# analog_front_end.net
KiCad netlist of a schematic drawn in Altium Designer
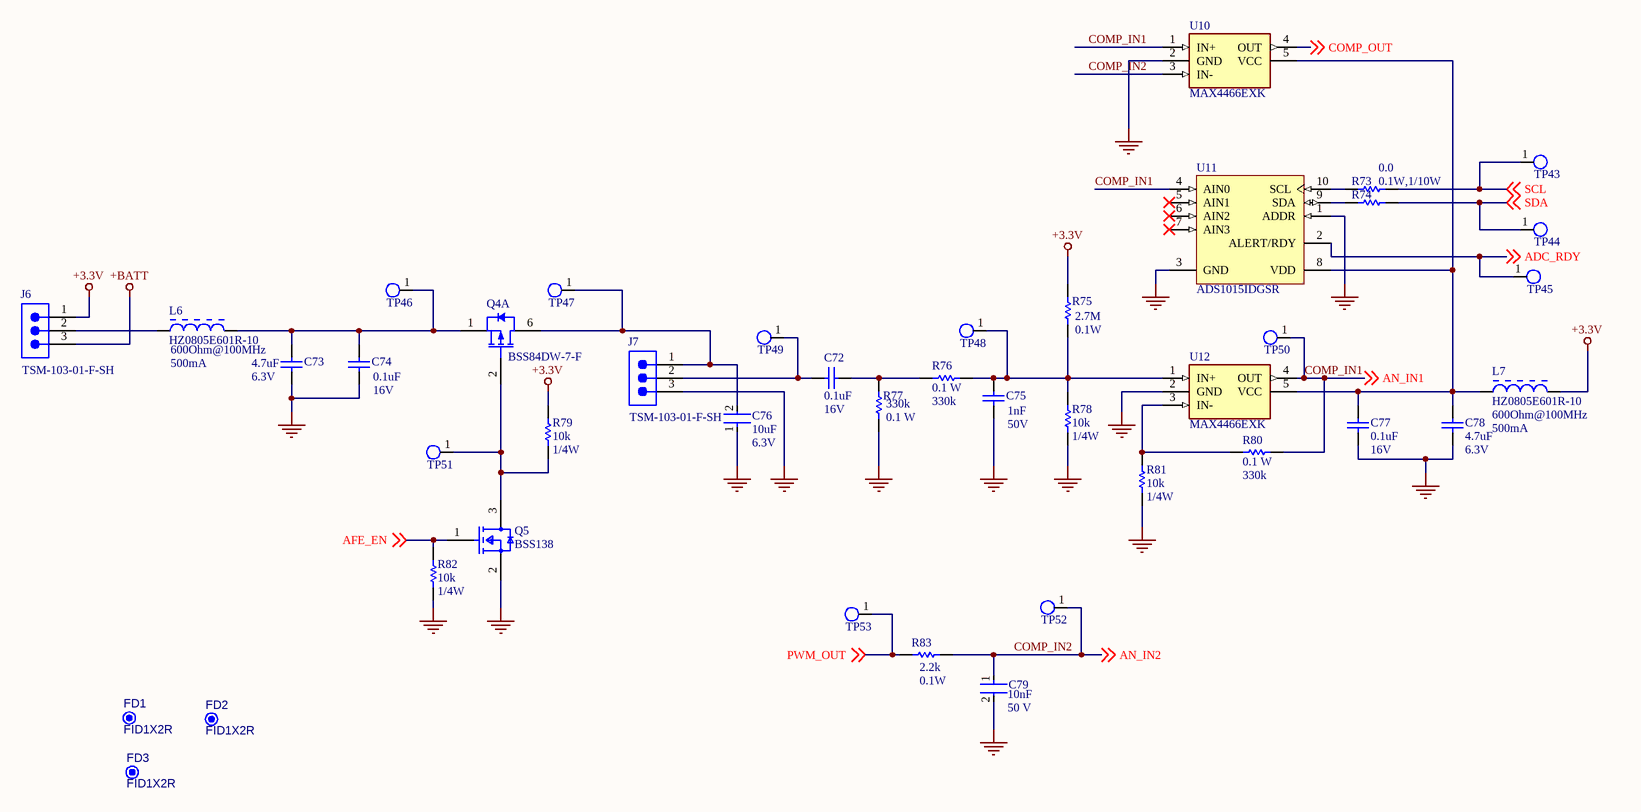
[diagram p0: analog_front_end.SchDoc]

(export (version "E")
  (design (tool "Eeschema 10.0.6"))
  (components
    (comp (ref "C72")
      (value "0.1uF")
      (footprint "CAPC1608X87X35ML15T15")
      (description "Ceramic Capacitor 0.1uF 16V +-10% X7R0603")
      (fields
        (field (name "PART NUMBER") "C0603C104M4RACTU")
        (field (name "MANUFACTURER") "Kemet")
        (field (name "VOLTAGE") "16V")
      )
      (libsource (lib "Altium Content Vault") (part "CAP"))
    )
    (comp (ref "C73")
      (value "4.7uF")
      (footprint "CAPC2013X145X50NL20T25")
      (fields
        (field (name "PART NUMBER") "C0805C475K9PACTU")
        (field (name "MANUFACTURER") "Kemet")
        (field (name "VOLTAGE") "6.3V")
      )
      (libsource (lib "Altium Content Vault") (part "CAP"))
    )
    (comp (ref "C74")
      (value "0.1uF")
      (footprint "CAPC1608X87X35ML15T15")
      (description "Ceramic Capacitor 0.1uF 16V +-10% X7R0603")
      (fields
        (field (name "PART NUMBER") "C0603C104M4RACTU")
        (field (name "MANUFACTURER") "Kemet")
        (field (name "VOLTAGE") "16V")
      )
      (libsource (lib "Altium Content Vault") (part "CAP"))
    )
    (comp (ref "C75")
      (value "1nF")
      (footprint "CAPC1608X90X35LL15T15")
      (fields
        (field (name "MANUFACTURER") "AVX Interconnect / Elco")
        (field (name "PART NUMBER") "06035C102KAT2A")
        (field (name "VOLTAGE") "50V")
      )
      (libsource (lib "Altium Content Vault") (part "CAP"))
    )
    (comp (ref "C76")
      (value "10uF")
      (footprint "FP-CL10-IPC_C")
      (description "Cap Ceramic 10uF 6.3V X5R ±20% Pad SMD 0603 +85°C T/R")
      (fields
        (field (name "VOLTAGE") "6.3V")
        (field (name "TOLERANCE") "20%")
        (field (name "MANUFACTURER") "Samsung")
      )
      (libsource (lib "Altium Content Vault") (part "b4654b650e69147ec39a6b967a45e02"))
    )
    (comp (ref "C77")
      (value "0.1uF")
      (footprint "CAPC1608X87X35ML15T15")
      (description "Ceramic Capacitor 0.1uF 16V +-10% X7R0603")
      (fields
        (field (name "PART NUMBER") "C0603C104M4RACTU")
        (field (name "MANUFACTURER") "Kemet")
        (field (name "VOLTAGE") "16V")
      )
      (libsource (lib "Altium Content Vault") (part "CAP"))
    )
    (comp (ref "C78")
      (value "4.7uF")
      (footprint "CAPC2013X145X50NL20T25")
      (fields
        (field (name "PART NUMBER") "C0805C475K9PACTU")
        (field (name "MANUFACTURER") "Kemet")
        (field (name "VOLTAGE") "6.3V")
      )
      (libsource (lib "Altium Content Vault") (part "CAP"))
    )
    (comp (ref "C79")
      (value "10nF")
      (footprint "FP-C0805C-DN-MFG")
      (description "CAP CER 10000PF 50V X7R 0805")
      (fields
        (field (name "VOLTAGE") "50 V")
        (field (name "PART NUMBER") "C0805C103K5RACAUTO")
        (field (name "MANUFACTURER") "KEMET")
      )
      (libsource (lib "Altium Content Vault") (part "b4654b650e69147ec39a6b967a45e02"))
    )
    (comp (ref "FD1")
      (value "FID1X2R")
      (footprint "FID1X2R")
      (description "Fiducial - Round 1x2mm")
      (libsource (lib "EMS") (part "CMP-00134-2"))
    )
    (comp (ref "FD2")
      (value "FID1X2R")
      (footprint "FID1X2R")
      (description "Fiducial - Round 1x2mm")
      (libsource (lib "EMS") (part "CMP-00134-2"))
    )
    (comp (ref "FD3")
      (value "FID1X2R")
      (footprint "FID1X2R")
      (description "Fiducial - Round 1x2mm")
      (libsource (lib "EMS") (part "CMP-00134-2"))
    )
    (comp (ref "J6")
      (value "TSM-103-01-F-SH")
      (footprint "SMTC-TSM-103-01-X-SH-A")
      (fields (field (name "MANUFACTURER") "Samtec") (field (name "PART NUMBER") "TSM-103-01-F-SH"))
      (libsource (lib "Altium Content Vault") (part "SMTC-TSM-103-01-X-SH-A"))
    )
    (comp (ref "J7")
      (value "TSM-103-01-F-SH")
      (footprint "SMTC-TSM-103-01-X-SH-A")
      (fields (field (name "MANUFACTURER") "Samtec") (field (name "PART NUMBER") "TSM-103-01-F-SH"))
      (libsource (lib "Altium Content Vault") (part "SMTC-TSM-103-01-X-SH-A"))
    )
    (comp (ref "L6")
      (value "HZ0805E601R-10")
      (footprint "LIRD-LI0805H151R-10-2_V")
      (fields
        (field (name "IMPEDANCE @ FREQUENCY") "600Ohm@100MHz")
        (field (name "MANUFACTURER") "Laird")
        (field (name "CURRENT RATING (MAX)") "500mA")
      )
      (libsource (lib "Altium Content Vault") (part "IND-FB-2"))
    )
    (comp (ref "L7")
      (value "HZ0805E601R-10")
      (footprint "LIRD-LI0805H151R-10-2_V")
      (fields
        (field (name "IMPEDANCE @ FREQUENCY") "600Ohm@100MHz")
        (field (name "MANUFACTURER") "Laird")
        (field (name "CURRENT RATING (MAX)") "500mA")
      )
      (libsource (lib "") (part "IND-FB-2_1"))
    )
    (comp (ref "Q4")
      (value "BSS84DW-7-F")
      (footprint "DIOD-SOT363-6_V")
      (description "Dual P-Channel Enhancement Mode MOSFET, 50 VDS, -55 to 150 degC, 6-Pin SOT363, RoHS, Tape and Reel")
      (fields (field (name "MANUFACTURER") "DiodesIncorporated"))
      (libsource (lib "Altium Content Vault") (part "PEMOS-SGD-SGD-6"))
    )
    (comp (ref "Q5")
      (value "BSS138")
      (footprint "FP-318-08-IPC_B")
      (description "MOSFET N-CH 50V 220MA SOT-23")
      (libsource (lib "Altium Content Vault") (part "3b9c635fedb024a5347a57b145af9cc"))
    )
    (comp (ref "R73")
      (value "0.0")
      (footprint "RESC1608X55X35LL10T10")
      (description "Chip Resistor, 0 Ohm, +/- 5%, 0.1 W, -55 to 155 degC, 0603 (1608 Metric), RoHS, Tape and Reel")
      (fields
        (field (name "POWER") "0.1W,1/10W")
        (field (name "MANUFACTURER") "Samsung-Electro-Mechanics-America,-Inc.")
        (field (name "TOLERANCE") "Jumper")
      )
      (libsource (lib "Altium Content Vault") (part "RES-2"))
    )
    (comp (ref "R74")
      (value "RC1608J000CS")
      (footprint "RESC1608X55X35LL10T10")
      (description "Chip Resistor, 0 Ohm, +/- 5%, 0.1 W, -55 to 155 degC, 0603 (1608 Metric), RoHS, Tape and Reel")
      (fields
        (field (name "POWER") "0.1W,1/10W")
        (field (name "MANUFACTURER") "Samsung-Electro-Mechanics-America,-Inc.")
      )
      (libsource (lib "Altium Content Vault") (part "RES-2"))
    )
    (comp (ref "R75")
      (value "2.7M")
      (footprint "RESC1609X50X30ML10T20")
      (fields
        (field (name "PART NUMBER") "CRCW06032M70JNEA")
        (field (name "MANUFACTURER") "Vishay Dale")
        (field (name "POWER") "0.1W")
      )
      (libsource (lib "Altium Content Vault") (part "RES"))
    )
    (comp (ref "R76")
      (value "330k")
      (footprint "RESC0603(1608)_M")
      (description "330K 0.1W 1% 0603 (1608 Metric)  SMD")
      (fields
        (field (name "POWER") "0.1 W")
        (field (name "TOLERANCE") "1 %")
        (field (name "Comment") "330K 1% 0603(1608)")
      )
      (libsource (lib "Altium Content Vault") (part "RES"))
    )
    (comp (ref "R77")
      (value "330k")
      (footprint "RESC0603(1608)_M")
      (description "330K 0.1W 1% 0603 (1608 Metric)  SMD")
      (fields
        (field (name "POWER") "0.1 W")
        (field (name "TOLERANCE") "1 %")
        (field (name "Comment") "330K 1% 0603(1608)")
      )
      (libsource (lib "Altium Content Vault") (part "RES"))
    )
    (comp (ref "R78")
      (value "10k")
      (footprint "RESC3216X70X50NL05T20")
      (description "Res Thick Film 1206 10k Ohms 5% 1/4W")
      (fields
        (field (name "PART NUMBER") "ERJ-8GEYJ103V")
        (field (name "MANUFACTURER") "Panasonic")
        (field (name "POWER") "1/4W")
      )
      (libsource (lib "Altium Content Vault") (part "RES"))
    )
    (comp (ref "R79")
      (value "10k")
      (footprint "RESC3216X70X50NL05T20")
      (description "Res Thick Film 1206 10k Ohms 5% 1/4W")
      (fields
        (field (name "PART NUMBER") "ERJ-8GEYJ103V")
        (field (name "MANUFACTURER") "Panasonic")
        (field (name "POWER") "1/4W")
      )
      (libsource (lib "Altium Content Vault") (part "RES"))
    )
    (comp (ref "R80")
      (value "330k")
      (footprint "RESC0603(1608)_M")
      (description "330K 0.1W 1% 0603 (1608 Metric)  SMD")
      (fields
        (field (name "POWER") "0.1 W")
        (field (name "TOLERANCE") "1 %")
        (field (name "Comment") "330K 1% 0603(1608)")
      )
      (libsource (lib "Altium Content Vault") (part "RES"))
    )
    (comp (ref "R81")
      (value "10k")
      (footprint "RESC3216X70X50NL05T20")
      (description "Res Thick Film 1206 10k Ohms 5% 1/4W")
      (fields
        (field (name "PART NUMBER") "ERJ-8GEYJ103V")
        (field (name "MANUFACTURER") "Panasonic")
        (field (name "POWER") "1/4W")
      )
      (libsource (lib "Altium Content Vault") (part "RES"))
    )
    (comp (ref "R82")
      (value "10k")
      (footprint "RESC3216X70X50NL05T20")
      (description "Res Thick Film 1206 10k Ohms 5% 1/4W")
      (fields
        (field (name "PART NUMBER") "ERJ-8GEYJ103V")
        (field (name "MANUFACTURER") "Panasonic")
        (field (name "POWER") "1/4W")
      )
      (libsource (lib "Altium Content Vault") (part "RES"))
    )
    (comp (ref "R83")
      (value "2.2k")
      (footprint "RESC1608X55X25LL10T15")
      (fields
        (field (name "TOLERANCE") "1%")
        (field (name "VOLTAGE") "50V")
        (field (name "MANUFACTURER") "Yageo")
        (field (name "POWER") "0.1W")
      )
      (libsource (lib "Altium Content Vault") (part "RES-2"))
    )
    (comp (ref "TP43")
      (value "Test_Point_SMD")
      (footprint "Test_Point_SMD")
      (libsource (lib "Edson") (part "Test_Point_SMD"))
    )
    (comp (ref "TP44")
      (value "Test_Point_SMD")
      (footprint "Test_Point_SMD")
      (libsource (lib "Edson") (part "Test_Point_SMD"))
    )
    (comp (ref "TP45")
      (value "Test_Point_SMD")
      (footprint "Test_Point_SMD")
      (libsource (lib "Edson") (part "Test_Point_SMD"))
    )
    (comp (ref "TP46")
      (value "Test_Point_SMD")
      (footprint "Test_Point_SMD")
      (libsource (lib "Edson") (part "Test_Point_SMD"))
    )
    (comp (ref "TP47")
      (value "Test_Point_SMD")
      (footprint "Test_Point_SMD")
      (libsource (lib "Edson") (part "Test_Point_SMD"))
    )
    (comp (ref "TP48")
      (value "Test_Point_SMD")
      (footprint "Test_Point_SMD")
      (libsource (lib "Edson") (part "Test_Point_SMD"))
    )
    (comp (ref "TP49")
      (value "Test_Point_SMD")
      (footprint "Test_Point_SMD")
      (libsource (lib "Edson") (part "Test_Point_SMD"))
    )
    (comp (ref "TP50")
      (value "Test_Point_SMD")
      (footprint "Test_Point_SMD")
      (libsource (lib "Edson") (part "Test_Point_SMD"))
    )
    (comp (ref "TP51")
      (value "Test_Point_SMD")
      (footprint "Test_Point_SMD")
      (libsource (lib "Edson") (part "Test_Point_SMD"))
    )
    (comp (ref "TP52")
      (value "Test_Point_SMD")
      (footprint "Test_Point_SMD")
      (libsource (lib "Edson") (part "Test_Point_SMD"))
    )
    (comp (ref "TP53")
      (value "Test_Point_SMD")
      (footprint "Test_Point_SMD")
      (libsource (lib "Edson") (part "Test_Point_SMD"))
    )
    (comp (ref "U10")
      (value "MAX4466EXK")
      (footprint "SamacSys:SOT95P280X145-5N")
      (description "Integrated Circuit")
      (libsource (lib "*") (part "MAX4466EXK"))
    )
    (comp (ref "U11")
      (value "ADS1015IDGSR")
      (footprint "TI-DGS10_N")
      (fields (field (name "MANUFACTURER") "Texas Instruments"))
      (libsource (lib "Altium Content Vault") (part "TI-ADS1015_1115-10"))
    )
    (comp (ref "U12")
      (value "MAX4466EXK")
      (footprint "SamacSys:SOT95P280X145-5N")
      (description "Integrated Circuit")
      (libsource (lib "*") (part "MAX4466EXK"))
    )
  )
  (nets
    (net (code "1") (name "+3.3V") (class "Default")
      (node (ref "J6") (pin "1") (pinfunction "1_1") (pintype "passive"))
      (node (ref "L7") (pin "1") (pinfunction "1_1") (pintype "passive"))
      (node (ref "R75") (pin "2") (pinfunction "2_2") (pintype "passive"))
      (node (ref "R79") (pin "1") (pinfunction "1_1") (pintype "passive"))
    )
    (net (code "2") (name "+BATT") (class "Default")
      (node (ref "J6") (pin "3") (pinfunction "3_3") (pintype "passive"))
    )
    (net (code "3") (name "ADC_RDY") (class "Default")
      (node (ref "TP45") (pin "1") (pinfunction "TP_1") (pintype "passive"))
      (node (ref "U11") (pin "2") (pinfunction "ALERT/RDY_2") (pintype "open_collector"))
    )
    (net (code "4") (name "AFE_EN") (class "Default")
      (node (ref "Q5") (pin "1") (pinfunction "G_1") (pintype "passive"))
      (node (ref "R82") (pin "1") (pinfunction "1_1") (pintype "passive"))
    )
    (net (code "5") (name "AN_IN1") (class "Default")
      (node (ref "R80") (pin "1") (pinfunction "1_1") (pintype "passive"))
      (node (ref "TP50") (pin "1") (pinfunction "TP_1") (pintype "passive"))
      (node (ref "U10") (pin "1") (pinfunction "IN+_1") (pintype "input"))
      (node (ref "U11") (pin "4") (pinfunction "AIN0_4") (pintype "input"))
      (node (ref "U12") (pin "4") (pinfunction "OUT_4") (pintype "output"))
    )
    (net (code "6") (name "AN_IN2") (class "Default")
      (node (ref "C79") (pin "1") (pinfunction "1_1") (pintype "passive"))
      (node (ref "R83") (pin "2") (pinfunction "2_2") (pintype "passive"))
      (node (ref "TP52") (pin "1") (pinfunction "TP_1") (pintype "passive"))
      (node (ref "U10") (pin "3") (pinfunction "IN-_3") (pintype "input"))
    )
    (net (code "7") (name "COMP_OUT") (class "Default")
      (node (ref "U10") (pin "4") (pinfunction "OUT_4") (pintype "output"))
    )
    (net (code "8") (name "GND") (class "Default")
      (node (ref "C73") (pin "1") (pinfunction "1_1") (pintype "passive"))
      (node (ref "C74") (pin "1") (pinfunction "1_1") (pintype "passive"))
      (node (ref "C75") (pin "1") (pinfunction "1_1") (pintype "passive"))
      (node (ref "C76") (pin "1") (pinfunction "1_1") (pintype "passive"))
      (node (ref "C77") (pin "1") (pinfunction "1_1") (pintype "passive"))
      (node (ref "C78") (pin "1") (pinfunction "1_1") (pintype "passive"))
      (node (ref "C79") (pin "2") (pinfunction "2_2") (pintype "passive"))
      (node (ref "J7") (pin "3") (pinfunction "3_3") (pintype "passive"))
      (node (ref "Q5") (pin "2") (pinfunction "S_2") (pintype "passive"))
      (node (ref "R77") (pin "1") (pinfunction "1_1") (pintype "passive"))
      (node (ref "R78") (pin "2") (pinfunction "2_2") (pintype "passive"))
      (node (ref "R81") (pin "2") (pinfunction "2_2") (pintype "passive"))
      (node (ref "R82") (pin "2") (pinfunction "2_2") (pintype "passive"))
      (node (ref "U10") (pin "2") (pinfunction "GND_2") (pintype "power_in"))
      (node (ref "U11") (pin "1") (pinfunction "ADDR_1") (pintype "input"))
      (node (ref "U11") (pin "3") (pinfunction "GND_3") (pintype "power_in"))
      (node (ref "U12") (pin "2") (pinfunction "GND_2") (pintype "power_in"))
    )
    (net (code "9") (name "Net-(C72-Pad2)") (class "Default")
      (node (ref "C72") (pin "2") (pinfunction "2_2") (pintype "passive"))
      (node (ref "R76") (pin "2") (pinfunction "2_2") (pintype "passive"))
      (node (ref "R77") (pin "2") (pinfunction "2_2") (pintype "passive"))
    )
    (net (code "10") (name "Net-(J6-Pad2)") (class "Default")
      (node (ref "J6") (pin "2") (pinfunction "2_2") (pintype "passive"))
      (node (ref "L6") (pin "1") (pinfunction "1_1") (pintype "passive"))
    )
    (net (code "11") (name "Net-(Q4A-D)") (class "Default")
      (node (ref "C76") (pin "2") (pinfunction "2_2") (pintype "passive"))
      (node (ref "J7") (pin "1") (pinfunction "1_1") (pintype "passive"))
      (node (ref "Q4") (pin "6") (pinfunction "D_6") (pintype "passive"))
      (node (ref "TP47") (pin "1") (pinfunction "TP_1") (pintype "passive"))
    )
    (net (code "12") (name "Net-(Q4A-G)") (class "Default")
      (node (ref "Q4") (pin "2") (pinfunction "G_2") (pintype "passive"))
      (node (ref "Q5") (pin "3") (pinfunction "D_3") (pintype "passive"))
      (node (ref "R79") (pin "2") (pinfunction "2_2") (pintype "passive"))
      (node (ref "TP51") (pin "1") (pinfunction "TP_1") (pintype "passive"))
    )
    (net (code "13") (name "Net-(Q4A-S)") (class "Default")
      (node (ref "C73") (pin "2") (pinfunction "2_2") (pintype "passive"))
      (node (ref "C74") (pin "2") (pinfunction "2_2") (pintype "passive"))
      (node (ref "L6") (pin "2") (pinfunction "2_2") (pintype "passive"))
      (node (ref "Q4") (pin "1") (pinfunction "S_1") (pintype "passive"))
      (node (ref "TP46") (pin "1") (pinfunction "TP_1") (pintype "passive"))
    )
    (net (code "14") (name "Net-(TP48-TP)") (class "Default")
      (node (ref "C75") (pin "2") (pinfunction "2_2") (pintype "passive"))
      (node (ref "R75") (pin "1") (pinfunction "1_1") (pintype "passive"))
      (node (ref "R76") (pin "1") (pinfunction "1_1") (pintype "passive"))
      (node (ref "R78") (pin "1") (pinfunction "1_1") (pintype "passive"))
      (node (ref "TP48") (pin "1") (pinfunction "TP_1") (pintype "passive"))
      (node (ref "U12") (pin "1") (pinfunction "IN+_1") (pintype "input"))
    )
    (net (code "15") (name "Net-(TP49-TP)") (class "Default")
      (node (ref "C72") (pin "1") (pinfunction "1_1") (pintype "passive"))
      (node (ref "J7") (pin "2") (pinfunction "2_2") (pintype "passive"))
      (node (ref "TP49") (pin "1") (pinfunction "TP_1") (pintype "passive"))
    )
    (net (code "16") (name "Net-(U10-VCC)") (class "Default")
      (node (ref "C77") (pin "2") (pinfunction "2_2") (pintype "passive"))
      (node (ref "C78") (pin "2") (pinfunction "2_2") (pintype "passive"))
      (node (ref "L7") (pin "2") (pinfunction "2_2") (pintype "passive"))
      (node (ref "U10") (pin "5") (pinfunction "VCC_5") (pintype "power_in"))
      (node (ref "U11") (pin "8") (pinfunction "VDD_8") (pintype "power_in"))
      (node (ref "U12") (pin "5") (pinfunction "VCC_5") (pintype "power_in"))
    )
    (net (code "17") (name "Net-(U11-SCL)") (class "Default")
      (node (ref "R73") (pin "1") (pinfunction "1_1") (pintype "passive"))
      (node (ref "U11") (pin "10") (pinfunction "SCL_10") (pintype "input"))
    )
    (net (code "18") (name "Net-(U11-SDA)") (class "Default")
      (node (ref "R74") (pin "1") (pinfunction "1_1") (pintype "passive"))
      (node (ref "U11") (pin "9") (pinfunction "SDA_9") (pintype "bidirectional"))
    )
    (net (code "19") (name "Net-(U12-IN-)") (class "Default")
      (node (ref "R80") (pin "2") (pinfunction "2_2") (pintype "passive"))
      (node (ref "R81") (pin "1") (pinfunction "1_1") (pintype "passive"))
      (node (ref "U12") (pin "3") (pinfunction "IN-_3") (pintype "input"))
    )
    (net (code "20") (name "PWM_OUT") (class "Default")
      (node (ref "R83") (pin "1") (pinfunction "1_1") (pintype "passive"))
      (node (ref "TP53") (pin "1") (pinfunction "TP_1") (pintype "passive"))
    )
    (net (code "21") (name "SCL") (class "Default")
      (node (ref "R73") (pin "2") (pinfunction "2_2") (pintype "passive"))
      (node (ref "TP43") (pin "1") (pinfunction "TP_1") (pintype "passive"))
    )
    (net (code "22") (name "SDA") (class "Default")
      (node (ref "R74") (pin "2") (pinfunction "2_2") (pintype "passive"))
      (node (ref "TP44") (pin "1") (pinfunction "TP_1") (pintype "passive"))
    )
    (net (code "23") (name "unconnected-(U11-AIN1-Pad5)") (class "Default")
      (node (ref "U11") (pin "5") (pinfunction "AIN1_5") (pintype "input+no_connect"))
    )
    (net (code "24") (name "unconnected-(U11-AIN2-Pad6)") (class "Default")
      (node (ref "U11") (pin "6") (pinfunction "AIN2_6") (pintype "input+no_connect"))
    )
    (net (code "25") (name "unconnected-(U11-AIN3-Pad7)") (class "Default")
      (node (ref "U11") (pin "7") (pinfunction "AIN3_7") (pintype "input+no_connect"))
    )
  )
)
